# ATmega4809_Curiosity_Nano_Debugger.net
KiCad netlist of a schematic drawn in Altium Designer
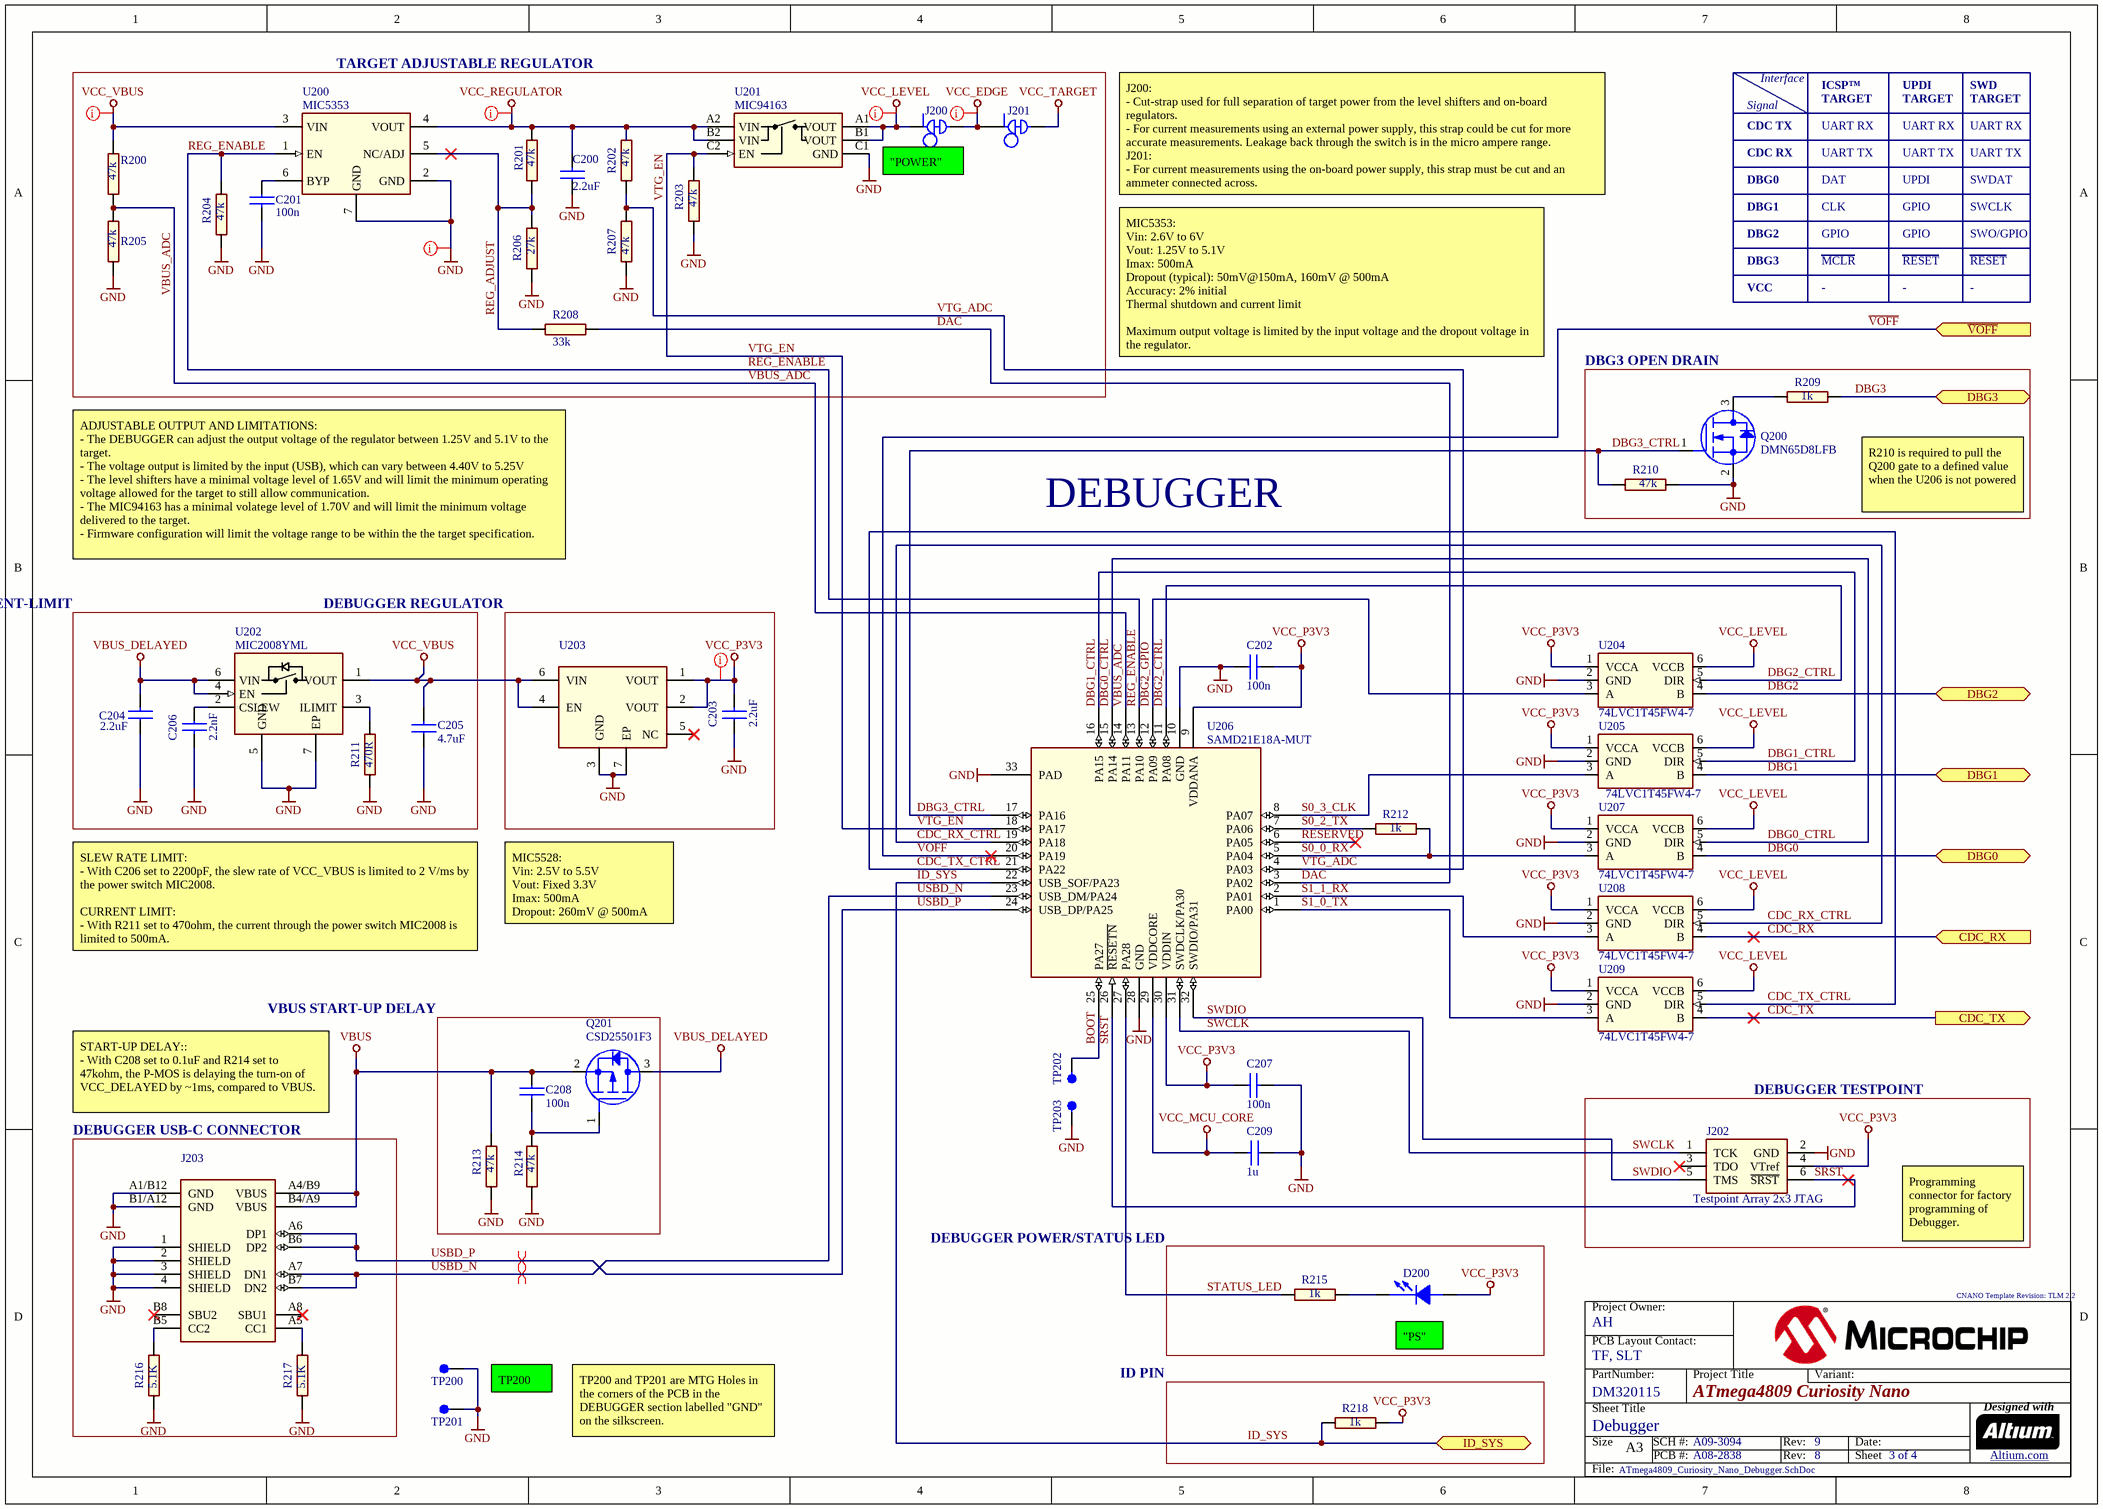
[diagram p0: ATmega4809_Curiosity_Nano_Debugger.SchDoc]

(export (version "E")
  (design (tool "Eeschema 10.0.6"))
  (components
    (comp (ref "C200")
      (value "2.2uF")
      (footprint "AP1-00148")
      (description "CAP CER 2.2UF 10V 10% X5R 0402")
      (fields (field (name "TOLERANCE") "+/-10%") (field (name "MANUFACTURER") "TDK"))
      (libsource (lib "AltiumDbLib") (part "CAP-NONPOL"))
    )
    (comp (ref "C201")
      (value "100n")
      (footprint "AP1-00148")
      (description "Ceramic capacitor, SMD 0402, X7R, 16V, +/-10%")
      (fields (field (name "TOLERANCE") "16V, +/-10%") (field (name "MANUFACTURER") "Yageo"))
      (libsource (lib "AltiumDbLib") (part "CAP-NONPOL"))
    )
    (comp (ref "C202")
      (value "100n")
      (footprint "AP1-00148")
      (description "Ceramic capacitor, SMD 0402, X7R, 16V, +/-10%")
      (fields (field (name "TOLERANCE") "16V, +/-10%") (field (name "MANUFACTURER") "Yageo"))
      (libsource (lib "AltiumDbLib") (part "CAP-NONPOL"))
    )
    (comp (ref "C203")
      (value "2.2uF")
      (footprint "AP1-00148")
      (description "CAP CER 2.2UF 10V 10% X5R 0402")
      (fields (field (name "TOLERANCE") "+/-10%") (field (name "MANUFACTURER") "TDK"))
      (libsource (lib "AltiumDbLib") (part "CAP-NONPOL"))
    )
    (comp (ref "C204")
      (value "2.2uF")
      (footprint "AP1-00148")
      (description "CAP CER 2.2UF 10V 10% X5R 0402")
      (fields (field (name "TOLERANCE") "+/-10%") (field (name "MANUFACTURER") "TDK"))
      (libsource (lib "AltiumDbLib") (part "CAP-NONPOL"))
    )
    (comp (ref "C205")
      (value "4.7uF")
      (footprint "AP1-00039")
      (description "Ceramic capacitor, SMD 0603, X5R, 10V, 10% (de31036)")
      (fields (field (name "TOLERANCE") "10%") (field (name "MANUFACTURER") "Yageo"))
      (libsource (lib "AltiumDbLib") (part "CAP-NONPOL"))
    )
    (comp (ref "C206")
      (value "2.2nF")
      (footprint "AP1-00148")
      (description "Ceramic capacitor, SMD 0402, C0G, 25V, +/-5%")
      (fields (field (name "TOLERANCE") "25V, +/-5%") (field (name "MANUFACTURER") "Kemet"))
      (libsource (lib "AltiumDbLib") (part "CAP-NONPOL"))
    )
    (comp (ref "C207")
      (value "100n")
      (footprint "AP1-00148")
      (description "Ceramic capacitor, SMD 0402, X7R, 16V, +/-10%")
      (fields (field (name "TOLERANCE") "16V, +/-10%") (field (name "MANUFACTURER") "Yageo"))
      (libsource (lib "AltiumDbLib") (part "CAP-NONPOL"))
    )
    (comp (ref "C208")
      (value "100n")
      (footprint "AP1-00148")
      (description "Ceramic capacitor, SMD 0402, X7R, 16V, +/-10%")
      (fields (field (name "TOLERANCE") "16V, +/-10%") (field (name "MANUFACTURER") "Yageo"))
      (libsource (lib "AltiumDbLib") (part "CAP-NONPOL"))
    )
    (comp (ref "C209")
      (value "1u")
      (footprint "AP1-00148")
      (description "Ceramic capacitor, SMD 0402, X5R, 6.3V, +/-10% (de26942)")
      (fields (field (name "TOLERANCE") "+/-10%") (field (name "MANUFACTURER") "Kemet"))
      (libsource (lib "AltiumDbLib") (part "CAP-NONPOL"))
    )
    (comp (ref "D200")
      (value "~")
      (footprint "AP4-00160")
      (description "LED, SMD 0402, Green, Wave length=569nm, 2.1mcd @ (1mA, 1.9Vf)rohm")
      (fields (field (name "MANUFACTURER") "ROHM") (field (name "MPN") "SML-P12MTT86R"))
      (libsource (lib "AltiumDbLib") (part "LED_12"))
    )
    (comp (ref "J200")
      (value "~")
      (footprint "AP8-00595")
      (description "Closed Link 0402")
      (libsource (lib "AltiumDbLib") (part "SMD-STRAP_CLOSED"))
    )
    (comp (ref "J201")
      (value "~")
      (footprint "AP8-01183")
      (description "Closed Link with w/hole for 1x2 100mil header")
      (libsource (lib "AltiumDbLib") (part "SMD-STRAP_CLOSED"))
    )
    (comp (ref "J202")
      (value "Testpoint Array 2x3 JTAG")
      (footprint "AP8-01249")
      (description "6-pin Testpoint Array, 0.8mm Pad, 1.27mm Pitch")
      (libsource (lib "AltiumDbLib") (part "TESTPOINT ARRAY 2x3 JTAG"))
    )
    (comp (ref "J203")
      (value "~")
      (footprint "AP8-01248")
      (description "USB2.0 Type-C, Surface mount signals and DIP shield")
      (fields (field (name "MANUFACTURER") "Cabcon A/S") (field (name "MPN") "L-KLS1-5409-R"))
      (libsource (lib "AltiumDbLib") (part "USB2.0-C_KLS1-5409"))
    )
    (comp (ref "Q200")
      (value "DMN65D8LFB")
      (footprint "AP5-00056")
      (description "N-channel MOSFET, DFN1006-3 (SOT883), 60V, 330mA, 4Ohm")
      (fields (field (name "MANUFACTURER") "Diodes Incorporated") (field (name "MPN") "DMN65D8LFB-7"))
      (libsource (lib "AltiumDbLib") (part "MOSFET_N_GSD"))
    )
    (comp (ref "Q201")
      (value "CSD25501F3")
      (footprint "AP5-00062")
      (description "P-Channel MOSFET, LGA, 20V, 3.6A, 76mOhm")
      (fields (field (name "MANUFACTURER") "Texas Instruments"))
      (libsource (lib "AltiumDbLib") (part "MOSFET_P_GSD"))
    )
    (comp (ref "R200")
      (value "47k")
      (footprint "AP2-00108")
      (description "Thick film resistor, SMD 0402, 1/16W, 1%")
      (fields (field (name "TOLERANCE") "1 %") (field (name "MANUFACTURER") "KOA"))
      (libsource (lib "") (part "R2_1"))
    )
    (comp (ref "R201")
      (value "47k")
      (footprint "AP2-00108")
      (description "Thick film resistor, SMD 0402, 1/16W, 1%")
      (fields (field (name "TOLERANCE") "1 %") (field (name "MANUFACTURER") "KOA"))
      (libsource (lib "") (part "R2_1"))
    )
    (comp (ref "R202")
      (value "47k")
      (footprint "AP2-00108")
      (description "Thick film resistor, SMD 0402, 1/16W, 1%")
      (fields (field (name "TOLERANCE") "1 %") (field (name "MANUFACTURER") "KOA"))
      (libsource (lib "AltiumDbLib") (part "R2"))
    )
    (comp (ref "R203")
      (value "47k")
      (footprint "AP2-00108")
      (description "Thick film resistor, SMD 0402, 1/16W, 1%")
      (fields (field (name "TOLERANCE") "1 %") (field (name "MANUFACTURER") "KOA"))
      (libsource (lib "") (part "R2_1"))
    )
    (comp (ref "R204")
      (value "47k")
      (footprint "AP2-00108")
      (description "Thick film resistor, SMD 0402, 1/16W, 1%")
      (fields (field (name "TOLERANCE") "1 %") (field (name "MANUFACTURER") "KOA"))
      (libsource (lib "") (part "R2_1"))
    )
    (comp (ref "R205")
      (value "47k")
      (footprint "AP2-00108")
      (description "Thick film resistor, SMD 0402, 1/16W, 1%")
      (fields (field (name "TOLERANCE") "1 %") (field (name "MANUFACTURER") "KOA"))
      (libsource (lib "AltiumDbLib") (part "R2"))
    )
    (comp (ref "R206")
      (value "27k")
      (footprint "AP2-00108")
      (description "Thick film resistor, SMD 0402, 1/16W, 1%")
      (fields (field (name "TOLERANCE") "1 %") (field (name "MANUFACTURER") "Yageo"))
      (libsource (lib "AltiumDbLib") (part "R2"))
    )
    (comp (ref "R207")
      (value "47k")
      (footprint "AP2-00108")
      (description "Thick film resistor, SMD 0402, 1/16W, 1%")
      (fields (field (name "TOLERANCE") "1 %") (field (name "MANUFACTURER") "KOA"))
      (libsource (lib "AltiumDbLib") (part "R2"))
    )
    (comp (ref "R208")
      (value "33k")
      (footprint "AP2-00108")
      (description "Thick film resistor, SMD 0402, 1/16W, 1%")
      (fields (field (name "TOLERANCE") "1 %") (field (name "MANUFACTURER") "Yageo"))
      (libsource (lib "") (part "R2_2"))
    )
    (comp (ref "R209")
      (value "1k")
      (footprint "AP2-00108")
      (description "Thick film resistor, SMD 0402, 1/16W, 1%")
      (fields (field (name "TOLERANCE") "1 %") (field (name "MANUFACTURER") "Yageo"))
      (libsource (lib "AltiumDbLib") (part "R2"))
    )
    (comp (ref "R210")
      (value "47k")
      (footprint "AP2-00108")
      (description "Thick film resistor, SMD 0402, 1/16W, 1%")
      (fields (field (name "TOLERANCE") "1 %") (field (name "MANUFACTURER") "KOA"))
      (libsource (lib "AltiumDbLib") (part "R2"))
    )
    (comp (ref "R211")
      (value "470R")
      (footprint "AP2-00108")
      (description "Thick film resistror, SMD 0402, 1/16W, 1%")
      (fields (field (name "TOLERANCE") "1%") (field (name "MANUFACTURER") "Yageo"))
      (libsource (lib "") (part "R2_1"))
    )
    (comp (ref "R212")
      (value "1k")
      (footprint "AP2-00108")
      (description "Thick film resistor, SMD 0402, 1/16W, 1%")
      (fields (field (name "TOLERANCE") "1 %") (field (name "MANUFACTURER") "Yageo"))
      (libsource (lib "") (part "R2_3"))
    )
    (comp (ref "R213")
      (value "47k")
      (footprint "AP2-00108")
      (description "Thick film resistor, SMD 0402, 1/16W, 1%")
      (fields (field (name "TOLERANCE") "1 %") (field (name "MANUFACTURER") "KOA"))
      (libsource (lib "") (part "R2_1"))
    )
    (comp (ref "R214")
      (value "47k")
      (footprint "AP2-00108")
      (description "Thick film resistor, SMD 0402, 1/16W, 1%")
      (fields (field (name "TOLERANCE") "1 %") (field (name "MANUFACTURER") "KOA"))
      (libsource (lib "") (part "R2_1"))
    )
    (comp (ref "R215")
      (value "1k")
      (footprint "AP2-00108")
      (description "Thick film resistor, SMD 0402, 1/16W, 1%")
      (fields (field (name "TOLERANCE") "1 %") (field (name "MANUFACTURER") "Yageo"))
      (libsource (lib "") (part "R2_3"))
    )
    (comp (ref "R216")
      (value "5.1K")
      (footprint "AP2-00108")
      (description "Thick film resistor, SMD 0402, 1W, 1%")
      (fields (field (name "TOLERANCE") "1%") (field (name "MANUFACTURER") "Panasonic"))
      (libsource (lib "") (part "R2_1"))
    )
    (comp (ref "R217")
      (value "5.1K")
      (footprint "AP2-00108")
      (description "Thick film resistor, SMD 0402, 1W, 1%")
      (fields (field (name "TOLERANCE") "1%") (field (name "MANUFACTURER") "Panasonic"))
      (libsource (lib "") (part "R2_1"))
    )
    (comp (ref "R218")
      (value "1k")
      (footprint "AP2-00108")
      (description "Thick film resistor, SMD 0402, 1/16W, 1%")
      (fields (field (name "TOLERANCE") "1 %") (field (name "MANUFACTURER") "Yageo"))
      (libsource (lib "") (part "R2_2"))
    )
    (comp (ref "TP200")
      (value "PCB implemented component.")
      (footprint "AP8-01250")
      (description "TH Test point - D3.6H2.7")
      (libsource (lib "AltiumDbLib") (part "TESTPOINT"))
    )
    (comp (ref "TP201")
      (value "PCB implemented component.")
      (footprint "AP8-01250")
      (description "TH Test point - D3.6H2.7")
      (libsource (lib "AltiumDbLib") (part "TESTPOINT"))
    )
    (comp (ref "TP202")
      (value "PCB implemented component.")
      (footprint "AP8-00870")
      (description "SMD Test point - 0.8mm")
      (libsource (lib "AltiumDbLib") (part "TESTPOINT"))
    )
    (comp (ref "TP203")
      (value "PCB implemented component.")
      (footprint "AP8-00870")
      (description "SMD Test point - 0.8mm")
      (libsource (lib "AltiumDbLib") (part "TESTPOINT"))
    )
    (comp (ref "U200")
      (value "MIC5353")
      (footprint "AP6-00504")
      (description "500mA Ultra Low Dropout LDO regulator, 2% accuracy, 1.6x1.6mm MLF")
      (fields (field (name "MANUFACTURER") "Microchip") (field (name "MPN") "MIC5353YMT-TR"))
      (libsource (lib "AltiumDbLib") (part "MIC5319"))
    )
    (comp (ref "U201")
      (value "MIC94163")
      (footprint "AP6-00513")
      (description "Loadswitch, Rds(on) = 14.5mohm, 1.0mm x 1.5mm WLCSP, reverse blocking")
      (fields (field (name "MANUFACTURER") "Microchip") (field (name "MPN") "MIC94163YCS-TR"))
      (libsource (lib "AltiumDbLib") (part "MIC94163"))
    )
    (comp (ref "U202")
      (value "MIC2008YML")
      (footprint "AP6-00576")
      (description "0.2A- 2.5A adjustable current limit power switch, 2mm x 2mm DFN")
      (fields (field (name "MANUFACTURER") "Microchip") (field (name "MPN") "MIC2008YML-TR"))
      (libsource (lib "AltiumDbLib") (part "MIC2008YML-TR VDFN-6"))
    )
    (comp (ref "U203")
      (value "~")
      (footprint "AP6-00481")
      (description "LDO 3.3V 0.5A 6TDFN")
      (fields (field (name "MANUFACTURER") "Microchip") (field (name "MPN") "MIC5528-3.3YMT-T5"))
      (libsource (lib "AltiumDbLib") (part "MIC5528"))
    )
    (comp (ref "U204")
      (value "74LVC1T45FW4-7")
      (footprint "AP6-00575")
      (description "Single-Bit Dual-Supply Transceive, 1.65-5.5 Translation and 3-State Outputs")
      (fields (field (name "MANUFACTURER") "Diodes Incorporated"))
      (libsource (lib "AltiumDbLib") (part "SN74LVC1T45DCKR"))
    )
    (comp (ref "U205")
      (value "74LVC1T45FW4-7")
      (footprint "AP6-00575")
      (description "Single-Bit Dual-Supply Transceive, 1.65-5.5 Translation and 3-State Outputs")
      (fields (field (name "MANUFACTURER") "Diodes Incorporated"))
      (libsource (lib "AltiumDbLib") (part "SN74LVC1T45DCKR"))
    )
    (comp (ref "U206")
      (value "SAMD21E18A-MUT")
      (footprint "AP6-00418")
      (description "32-bit RISC MCU 32pin")
      (fields (field (name "MANUFACTURER") "Microchip") (field (name "MPN") "ATSAMD21E18A-MUT"))
      (libsource (lib "AltiumDbLib") (part "SAMD21E_QFN32"))
    )
    (comp (ref "U207")
      (value "74LVC1T45FW4-7")
      (footprint "AP6-00575")
      (description "Single-Bit Dual-Supply Transceive, 1.65-5.5 Translation and 3-State Outputs")
      (fields (field (name "MANUFACTURER") "Diodes Incorporated"))
      (libsource (lib "AltiumDbLib") (part "SN74LVC1T45DCKR"))
    )
    (comp (ref "U208")
      (value "74LVC1T45FW4-7")
      (footprint "AP6-00575")
      (description "Single-Bit Dual-Supply Transceive, 1.65-5.5 Translation and 3-State Outputs")
      (fields (field (name "MANUFACTURER") "Diodes Incorporated"))
      (libsource (lib "AltiumDbLib") (part "SN74LVC1T45DCKR"))
    )
    (comp (ref "U209")
      (value "74LVC1T45FW4-7")
      (footprint "AP6-00575")
      (description "Single-Bit Dual-Supply Transceive, 1.65-5.5 Translation and 3-State Outputs")
      (fields (field (name "MANUFACTURER") "Diodes Incorporated"))
      (libsource (lib "AltiumDbLib") (part "SN74LVC1T45DCKR"))
    )
  )
  (nets
    (net (code "1") (name "/BOOT") (class "Default")
      (node (ref "TP202") (pin "1") (pinfunction "1_1") (pintype "passive"))
      (node (ref "U206") (pin "25") (pinfunction "PA27_25") (pintype "bidirectional"))
    )
    (net (code "2") (name "/CDC_RX") (class "Default")
      (node (ref "U208") (pin "4") (pinfunction "B_4") (pintype "bidirectional"))
    )
    (net (code "3") (name "/CDC_RX_CTRL") (class "Default")
      (node (ref "U206") (pin "19") (pinfunction "PA18_19") (pintype "bidirectional"))
      (node (ref "U208") (pin "5") (pinfunction "DIR_5") (pintype "input"))
    )
    (net (code "4") (name "/CDC_TX") (class "Default")
      (node (ref "U209") (pin "4") (pinfunction "B_4") (pintype "bidirectional"))
    )
    (net (code "5") (name "/CDC_TX_CTRL") (class "Default")
      (node (ref "U206") (pin "21") (pinfunction "PA22_21") (pintype "bidirectional"))
      (node (ref "U209") (pin "5") (pinfunction "DIR_5") (pintype "input"))
    )
    (net (code "6") (name "/DAC") (class "Default")
      (node (ref "R208") (pin "2") (pinfunction "2_2") (pintype "passive"))
      (node (ref "U206") (pin "3") (pinfunction "PA02_3") (pintype "bidirectional"))
    )
    (net (code "7") (name "/DBG0") (class "Default")
      (node (ref "U207") (pin "4") (pinfunction "B_4") (pintype "bidirectional"))
    )
    (net (code "8") (name "/DBG0_CTRL") (class "Default")
      (node (ref "U206") (pin "15") (pinfunction "PA14_15") (pintype "bidirectional"))
      (node (ref "U207") (pin "5") (pinfunction "DIR_5") (pintype "input"))
    )
    (net (code "9") (name "/DBG1") (class "Default")
      (node (ref "U205") (pin "4") (pinfunction "B_4") (pintype "bidirectional"))
    )
    (net (code "10") (name "/DBG1_CTRL") (class "Default")
      (node (ref "U205") (pin "5") (pinfunction "DIR_5") (pintype "input"))
      (node (ref "U206") (pin "16") (pinfunction "PA15_16") (pintype "bidirectional"))
    )
    (net (code "11") (name "/DBG2") (class "Default")
      (node (ref "U204") (pin "4") (pinfunction "B_4") (pintype "bidirectional"))
    )
    (net (code "12") (name "/DBG2_CTRL") (class "Default")
      (node (ref "U204") (pin "5") (pinfunction "DIR_5") (pintype "input"))
      (node (ref "U206") (pin "11") (pinfunction "PA08_11") (pintype "bidirectional"))
    )
    (net (code "13") (name "/DBG2_GPIO") (class "Default")
      (node (ref "U204") (pin "3") (pinfunction "A_3") (pintype "bidirectional"))
      (node (ref "U206") (pin "12") (pinfunction "PA09_12") (pintype "bidirectional"))
    )
    (net (code "14") (name "/DBG3") (class "Default")
      (node (ref "R209") (pin "2") (pinfunction "2_2") (pintype "passive"))
    )
    (net (code "15") (name "/DBG3_CTRL") (class "Default")
      (node (ref "Q200") (pin "1") (pinfunction "G_1") (pintype "passive"))
      (node (ref "R210") (pin "1") (pinfunction "1_1") (pintype "passive"))
      (node (ref "U206") (pin "17") (pinfunction "PA16_17") (pintype "bidirectional"))
    )
    (net (code "16") (name "/ID_SYS") (class "Default")
      (node (ref "R218") (pin "1") (pinfunction "1_1") (pintype "passive"))
      (node (ref "U206") (pin "22") (pinfunction "USB_SOF/PA23_22") (pintype "bidirectional"))
    )
    (net (code "17") (name "/REG_ADJUST") (class "Default")
      (node (ref "R201") (pin "2") (pinfunction "2_2") (pintype "passive"))
      (node (ref "R206") (pin "2") (pinfunction "2_2") (pintype "passive"))
      (node (ref "R208") (pin "1") (pinfunction "1_1") (pintype "passive"))
      (node (ref "U200") (pin "5") (pinfunction "NC/ADJ_5") (pintype "passive"))
    )
    (net (code "18") (name "/REG_ENABLE") (class "Default")
      (node (ref "R204") (pin "1") (pinfunction "1_1") (pintype "passive"))
      (node (ref "U200") (pin "1") (pinfunction "EN_1") (pintype "input"))
      (node (ref "U206") (pin "13") (pinfunction "PA10_13") (pintype "bidirectional"))
    )
    (net (code "19") (name "/RESERVED") (class "Default")
      (node (ref "U206") (pin "6") (pinfunction "PA05_6") (pintype "bidirectional+no_connect"))
    )
    (net (code "20") (name "/S0_0_RX") (class "Default")
      (node (ref "R212") (pin "1") (pinfunction "1_1") (pintype "passive"))
      (node (ref "U206") (pin "5") (pinfunction "PA04_5") (pintype "bidirectional"))
      (node (ref "U207") (pin "3") (pinfunction "A_3") (pintype "bidirectional"))
    )
    (net (code "21") (name "/S0_2_TX") (class "Default")
      (node (ref "R212") (pin "2") (pinfunction "2_2") (pintype "passive"))
      (node (ref "U206") (pin "7") (pinfunction "PA06_7") (pintype "bidirectional"))
    )
    (net (code "22") (name "/S0_3_CLK") (class "Default")
      (node (ref "U205") (pin "3") (pinfunction "A_3") (pintype "bidirectional"))
      (node (ref "U206") (pin "8") (pinfunction "PA07_8") (pintype "bidirectional"))
    )
    (net (code "23") (name "/S1_0_TX") (class "Default")
      (node (ref "U206") (pin "1") (pinfunction "PA00_1") (pintype "bidirectional"))
      (node (ref "U209") (pin "3") (pinfunction "A_3") (pintype "bidirectional"))
    )
    (net (code "24") (name "/S1_1_RX") (class "Default")
      (node (ref "U206") (pin "2") (pinfunction "PA01_2") (pintype "bidirectional"))
      (node (ref "U208") (pin "3") (pinfunction "A_3") (pintype "bidirectional"))
    )
    (net (code "25") (name "/STATUS_LED") (class "Default")
      (node (ref "R215") (pin "2") (pinfunction "2_2") (pintype "passive"))
      (node (ref "U206") (pin "27") (pinfunction "PA28_27") (pintype "bidirectional"))
    )
    (net (code "26") (name "/SWCLK") (class "Default")
      (node (ref "J202") (pin "1") (pinfunction "TCK_1") (pintype "passive"))
      (node (ref "U206") (pin "31") (pinfunction "SWDCLK/PA30_31") (pintype "bidirectional"))
    )
    (net (code "27") (name "/SWDIO") (class "Default")
      (node (ref "J202") (pin "5") (pinfunction "TMS_5") (pintype "passive"))
      (node (ref "U206") (pin "32") (pinfunction "SWDIO/PA31_32") (pintype "bidirectional"))
    )
    (net (code "28") (name "/USBD_N") (class "Default")
      (node (ref "J203") (pin "A7") (pinfunction "DN1_A7") (pintype "bidirectional"))
      (node (ref "J203") (pin "B7") (pinfunction "DN2_B7") (pintype "bidirectional"))
      (node (ref "U206") (pin "23") (pinfunction "USB_DM/PA24_23") (pintype "bidirectional"))
    )
    (net (code "29") (name "/USBD_P") (class "Default")
      (node (ref "J203") (pin "A6") (pinfunction "DP1_A6") (pintype "bidirectional"))
      (node (ref "J203") (pin "B6") (pinfunction "DP2_B6") (pintype "bidirectional"))
      (node (ref "U206") (pin "24") (pinfunction "USB_DP/PA25_24") (pintype "bidirectional"))
    )
    (net (code "30") (name "/VBUS_ADC") (class "Default")
      (node (ref "R200") (pin "2") (pinfunction "2_2") (pintype "passive"))
      (node (ref "R205") (pin "2") (pinfunction "2_2") (pintype "passive"))
      (node (ref "U206") (pin "14") (pinfunction "PA11_14") (pintype "bidirectional"))
    )
    (net (code "31") (name "/VTG_ADC") (class "Default")
      (node (ref "R202") (pin "1") (pinfunction "1_1") (pintype "passive"))
      (node (ref "R207") (pin "2") (pinfunction "2_2") (pintype "passive"))
      (node (ref "U206") (pin "4") (pinfunction "PA03_4") (pintype "bidirectional"))
    )
    (net (code "32") (name "/VTG_EN") (class "Default")
      (node (ref "R203") (pin "1") (pinfunction "1_1") (pintype "passive"))
      (node (ref "U201") (pin "C2") (pinfunction "EN_C2") (pintype "input"))
      (node (ref "U206") (pin "18") (pinfunction "PA17_18") (pintype "bidirectional"))
    )
    (net (code "33") (name "/~{SRST}") (class "Default")
      (node (ref "J202") (pin "6") (pinfunction "~{SRST}_6") (pintype "passive"))
      (node (ref "U206") (pin "26") (pinfunction "~{RESETN}_26") (pintype "input"))
    )
    (net (code "34") (name "/~{VOFF}") (class "Default")
      (node (ref "U206") (pin "20") (pinfunction "PA19_20") (pintype "bidirectional+no_connect"))
    )
    (net (code "35") (name "GND") (class "Default")
      (node (ref "C200") (pin "1") (pinfunction "1_1") (pintype "passive"))
      (node (ref "C201") (pin "2") (pinfunction "2_2") (pintype "passive"))
      (node (ref "C202") (pin "1") (pinfunction "1_1") (pintype "passive"))
      (node (ref "C203") (pin "1") (pinfunction "1_1") (pintype "passive"))
      (node (ref "C204") (pin "1") (pinfunction "1_1") (pintype "passive"))
      (node (ref "C205") (pin "1") (pinfunction "1_1") (pintype "passive"))
      (node (ref "C206") (pin "2") (pinfunction "2_2") (pintype "passive"))
      (node (ref "C207") (pin "2") (pinfunction "2_2") (pintype "passive"))
      (node (ref "C209") (pin "1") (pinfunction "1_1") (pintype "passive"))
      (node (ref "J202") (pin "2") (pinfunction "GND_2") (pintype "power_in"))
      (node (ref "J203") (pin "1") (pinfunction "SHIELD_1") (pintype "passive"))
      (node (ref "J203") (pin "2") (pinfunction "SHIELD_2") (pintype "passive"))
      (node (ref "J203") (pin "3") (pinfunction "SHIELD_3") (pintype "passive"))
      (node (ref "J203") (pin "4") (pinfunction "SHIELD_4") (pintype "passive"))
      (node (ref "J203") (pin "A1/B12") (pinfunction "GND_A1/B12") (pintype "power_in"))
      (node (ref "J203") (pin "B1/A12") (pinfunction "GND_B1/A12") (pintype "power_in"))
      (node (ref "Q200") (pin "2") (pinfunction "S_2") (pintype "passive"))
      (node (ref "R203") (pin "2") (pinfunction "2_2") (pintype "passive"))
      (node (ref "R204") (pin "2") (pinfunction "2_2") (pintype "passive"))
      (node (ref "R205") (pin "1") (pinfunction "1_1") (pintype "passive"))
      (node (ref "R206") (pin "1") (pinfunction "1_1") (pintype "passive"))
      (node (ref "R207") (pin "1") (pinfunction "1_1") (pintype "passive"))
      (node (ref "R210") (pin "2") (pinfunction "2_2") (pintype "passive"))
      (node (ref "R211") (pin "2") (pinfunction "2_2") (pintype "passive"))
      (node (ref "R213") (pin "2") (pinfunction "2_2") (pintype "passive"))
      (node (ref "R214") (pin "2") (pinfunction "2_2") (pintype "passive"))
      (node (ref "R216") (pin "2") (pinfunction "2_2") (pintype "passive"))
      (node (ref "R217") (pin "2") (pinfunction "2_2") (pintype "passive"))
      (node (ref "TP200") (pin "1") (pinfunction "1_1") (pintype "passive"))
      (node (ref "TP201") (pin "1") (pinfunction "1_1") (pintype "passive"))
      (node (ref "TP203") (pin "1") (pinfunction "1_1") (pintype "passive"))
      (node (ref "U200") (pin "2") (pinfunction "GND_2") (pintype "power_in"))
      (node (ref "U200") (pin "7") (pinfunction "GND_7") (pintype "power_in"))
      (node (ref "U201") (pin "C1") (pinfunction "GND_C1") (pintype "power_in"))
      (node (ref "U202") (pin "5") (pinfunction "GND_5") (pintype "power_in"))
      (node (ref "U202") (pin "7") (pinfunction "EP_7") (pintype "power_in"))
      (node (ref "U203") (pin "3") (pinfunction "GND_3") (pintype "passive"))
      (node (ref "U203") (pin "7") (pinfunction "EP_7") (pintype "passive"))
      (node (ref "U204") (pin "2") (pinfunction "GND_2") (pintype "power_in"))
      (node (ref "U205") (pin "2") (pinfunction "GND_2") (pintype "power_in"))
      (node (ref "U206") (pin "10") (pinfunction "GND_10") (pintype "power_in"))
      (node (ref "U206") (pin "28") (pinfunction "GND_28") (pintype "power_in"))
      (node (ref "U206") (pin "33") (pinfunction "PAD_33") (pintype "passive"))
      (node (ref "U207") (pin "2") (pinfunction "GND_2") (pintype "power_in"))
      (node (ref "U208") (pin "2") (pinfunction "GND_2") (pintype "power_in"))
      (node (ref "U209") (pin "2") (pinfunction "GND_2") (pintype "power_in"))
    )
    (net (code "36") (name "Net-(D200-CATHODE)") (class "Default")
      (node (ref "D200") (pin "1") (pinfunction "CATHODE_1") (pintype "passive"))
      (node (ref "R215") (pin "1") (pinfunction "1_1") (pintype "passive"))
    )
    (net (code "37") (name "Net-(J203-CC1)") (class "Default")
      (node (ref "J203") (pin "A5") (pinfunction "CC1_A5") (pintype "passive"))
      (node (ref "R217") (pin "1") (pinfunction "1_1") (pintype "passive"))
    )
    (net (code "38") (name "Net-(J203-CC2)") (class "Default")
      (node (ref "J203") (pin "B5") (pinfunction "CC2_B5") (pintype "passive"))
      (node (ref "R216") (pin "1") (pinfunction "1_1") (pintype "passive"))
    )
    (net (code "39") (name "Net-(Q200-D)") (class "Default")
      (node (ref "Q200") (pin "3") (pinfunction "D_3") (pintype "passive"))
      (node (ref "R209") (pin "1") (pinfunction "1_1") (pintype "passive"))
    )
    (net (code "40") (name "Net-(Q201-G)") (class "Default")
      (node (ref "C208") (pin "2") (pinfunction "2_2") (pintype "passive"))
      (node (ref "Q201") (pin "1") (pinfunction "G_1") (pintype "passive"))
      (node (ref "R214") (pin "1") (pinfunction "1_1") (pintype "passive"))
    )
    (net (code "41") (name "Net-(U200-BYP)") (class "Default")
      (node (ref "C201") (pin "1") (pinfunction "1_1") (pintype "passive"))
      (node (ref "U200") (pin "6") (pinfunction "BYP_6") (pintype "passive"))
    )
    (net (code "42") (name "Net-(U202-CSLEW)") (class "Default")
      (node (ref "C206") (pin "1") (pinfunction "1_1") (pintype "passive"))
      (node (ref "U202") (pin "2") (pinfunction "CSLEW_2") (pintype "passive"))
    )
    (net (code "43") (name "Net-(U202-ILIMIT)") (class "Default")
      (node (ref "R211") (pin "1") (pinfunction "1_1") (pintype "passive"))
      (node (ref "U202") (pin "3") (pinfunction "ILIMIT_3") (pintype "passive"))
    )
    (net (code "44") (name "VBUS") (class "Default")
      (node (ref "C208") (pin "1") (pinfunction "1_1") (pintype "passive"))
      (node (ref "J203") (pin "A4/B9") (pinfunction "VBUS_A4/B9") (pintype "power_in"))
      (node (ref "J203") (pin "B4/A9") (pinfunction "VBUS_B4/A9") (pintype "power_in"))
      (node (ref "Q201") (pin "2") (pinfunction "S_2") (pintype "passive"))
      (node (ref "R213") (pin "1") (pinfunction "1_1") (pintype "passive"))
    )
    (net (code "45") (name "VBUS_DELAYED") (class "Default")
      (node (ref "C204") (pin "2") (pinfunction "2_2") (pintype "passive"))
      (node (ref "Q201") (pin "3") (pinfunction "D_3") (pintype "passive"))
      (node (ref "U202") (pin "4") (pinfunction "EN_4") (pintype "input"))
      (node (ref "U202") (pin "6") (pinfunction "VIN_6") (pintype "power_in"))
    )
    (net (code "46") (name "VCC_EDGE") (class "Default")
      (node (ref "J200") (pin "2") (pinfunction "2_2") (pintype "passive"))
      (node (ref "J201") (pin "1") (pinfunction "1_1") (pintype "passive"))
    )
    (net (code "47") (name "VCC_LEVEL") (class "Default")
      (node (ref "J200") (pin "1") (pinfunction "1_1") (pintype "passive"))
      (node (ref "U201") (pin "A1") (pinfunction "VOUT_A1") (pintype "passive"))
      (node (ref "U201") (pin "B1") (pinfunction "VOUT_B1") (pintype "passive"))
      (node (ref "U204") (pin "6") (pinfunction "VCCB_6") (pintype "power_in"))
      (node (ref "U205") (pin "6") (pinfunction "VCCB_6") (pintype "power_in"))
      (node (ref "U207") (pin "6") (pinfunction "VCCB_6") (pintype "power_in"))
      (node (ref "U208") (pin "6") (pinfunction "VCCB_6") (pintype "power_in"))
      (node (ref "U209") (pin "6") (pinfunction "VCCB_6") (pintype "power_in"))
    )
    (net (code "48") (name "VCC_MCU_CORE") (class "Default")
      (node (ref "C209") (pin "2") (pinfunction "2_2") (pintype "passive"))
      (node (ref "U206") (pin "29") (pinfunction "VDDCORE_29") (pintype "power_in"))
    )
    (net (code "49") (name "VCC_P3V3") (class "Default")
      (node (ref "C202") (pin "2") (pinfunction "2_2") (pintype "passive"))
      (node (ref "C203") (pin "2") (pinfunction "2_2") (pintype "passive"))
      (node (ref "C207") (pin "1") (pinfunction "1_1") (pintype "passive"))
      (node (ref "D200") (pin "2") (pinfunction "ANODE_2") (pintype "passive"))
      (node (ref "J202") (pin "4") (pinfunction "VTref_4") (pintype "passive"))
      (node (ref "R218") (pin "2") (pinfunction "2_2") (pintype "passive"))
      (node (ref "U203") (pin "1") (pinfunction "VOUT_1") (pintype "power_in"))
      (node (ref "U203") (pin "2") (pinfunction "VOUT_2") (pintype "power_in"))
      (node (ref "U204") (pin "1") (pinfunction "VCCA_1") (pintype "power_in"))
      (node (ref "U205") (pin "1") (pinfunction "VCCA_1") (pintype "power_in"))
      (node (ref "U206") (pin "30") (pinfunction "VDDIN_30") (pintype "power_in"))
      (node (ref "U206") (pin "9") (pinfunction "VDDANA_9") (pintype "power_in"))
      (node (ref "U207") (pin "1") (pinfunction "VCCA_1") (pintype "power_in"))
      (node (ref "U208") (pin "1") (pinfunction "VCCA_1") (pintype "power_in"))
      (node (ref "U209") (pin "1") (pinfunction "VCCA_1") (pintype "power_in"))
    )
    (net (code "50") (name "VCC_REGULATOR") (class "Default")
      (node (ref "C200") (pin "2") (pinfunction "2_2") (pintype "passive"))
      (node (ref "R201") (pin "1") (pinfunction "1_1") (pintype "passive"))
      (node (ref "R202") (pin "2") (pinfunction "2_2") (pintype "passive"))
      (node (ref "U200") (pin "4") (pinfunction "VOUT_4") (pintype "power_in"))
      (node (ref "U201") (pin "A2") (pinfunction "VIN_A2") (pintype "passive"))
      (node (ref "U201") (pin "B2") (pinfunction "VIN_B2") (pintype "passive"))
    )
    (net (code "51") (name "VCC_TARGET") (class "Default")
      (node (ref "J201") (pin "2") (pinfunction "2_2") (pintype "passive"))
    )
    (net (code "52") (name "VCC_VBUS") (class "Default")
      (node (ref "C205") (pin "2") (pinfunction "2_2") (pintype "passive"))
      (node (ref "R200") (pin "1") (pinfunction "1_1") (pintype "passive"))
      (node (ref "U200") (pin "3") (pinfunction "VIN_3") (pintype "power_in"))
      (node (ref "U202") (pin "1") (pinfunction "VOUT_1") (pintype "power_in"))
      (node (ref "U203") (pin "4") (pinfunction "EN_4") (pintype "passive"))
      (node (ref "U203") (pin "6") (pinfunction "VIN_6") (pintype "power_in"))
    )
    (net (code "53") (name "unconnected-(J202-TDO-Pad3)") (class "Default")
      (node (ref "J202") (pin "3") (pinfunction "TDO_3") (pintype "passive+no_connect"))
    )
    (net (code "54") (name "unconnected-(J203-SBU1-PadA8)") (class "Default")
      (node (ref "J203") (pin "A8") (pinfunction "SBU1_A8") (pintype "passive+no_connect"))
    )
    (net (code "55") (name "unconnected-(J203-SBU2-PadB8)") (class "Default")
      (node (ref "J203") (pin "B8") (pinfunction "SBU2_B8") (pintype "passive+no_connect"))
    )
    (net (code "56") (name "unconnected-(U203-NC-Pad5)") (class "Default")
      (node (ref "U203") (pin "5") (pinfunction "NC_5") (pintype "passive+no_connect"))
    )
  )
)
